# schematic_e00_1.net
KiCad netlist of a schematic drawn in Altium Designer
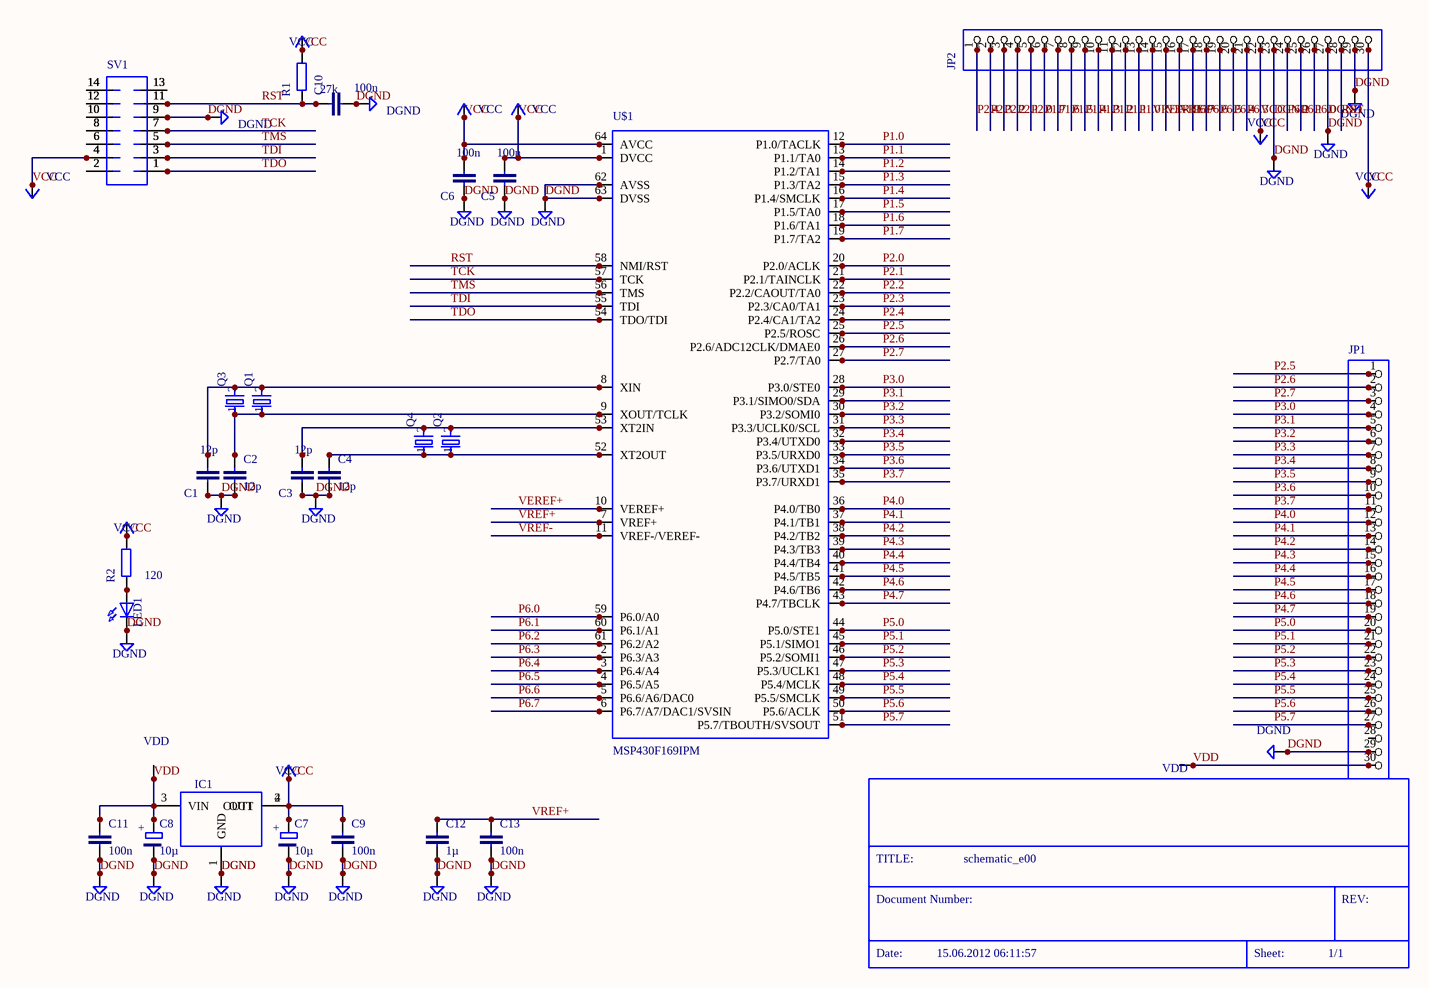
[diagram p0: schematic_e00_1.SchDoc]

(export (version "E")
  (design (tool "Eeschema 10.0.6"))
  (components
    (comp (ref "C1") (value "12p") (footprint "C0805") (libsource (lib "rcl") (part "C-EUC0805")))
    (comp (ref "C2") (value "12p") (footprint "C0805") (libsource (lib "rcl") (part "C-EUC0805")))
    (comp (ref "C3") (value "12p") (footprint "C0805") (libsource (lib "rcl") (part "C-EUC0805")))
    (comp (ref "C4") (value "12p") (footprint "C0805") (libsource (lib "rcl") (part "C-EUC0805")))
    (comp (ref "C5") (value "100n") (footprint "C0805") (libsource (lib "rcl") (part "C-EUC0805")))
    (comp (ref "C6") (value "100n") (footprint "C0805") (libsource (lib "rcl") (part "C-EUC0805")))
    (comp (ref "C7")
      (value "10µ")
      (footprint "153CLV-0505")
      (libsource (lib "rcl") (part "CPOL-EU153CLV-0505"))
    )
    (comp (ref "C8")
      (value "10µ")
      (footprint "153CLV-0505")
      (libsource (lib "rcl") (part "CPOL-EU153CLV-0505"))
    )
    (comp (ref "C9") (value "100n") (footprint "C0805") (libsource (lib "rcl") (part "C-EUC0805")))
    (comp (ref "C10") (value "100n") (footprint "C0805") (libsource (lib "rcl") (part "C-EUC0805")))
    (comp (ref "C11") (value "100n") (footprint "C0805") (libsource (lib "rcl") (part "C-EUC0805")))
    (comp (ref "C12") (value "1µ") (footprint "C0805") (libsource (lib "rcl") (part "C-EUC0805")))
    (comp (ref "C13") (value "100n") (footprint "C0805") (libsource (lib "rcl") (part "C-EUC0805")))
    (comp (ref "FRAME1") (value "~") (libsource (lib "") (part "DINA4_L_1")))
    (comp (ref "IC1") (value "~") (footprint "SOT223") (libsource (lib "national-2") (part "LM1117")))
    (comp (ref "JP1") (value "~") (footprint "1X30") (libsource (lib "pinhead") (part "PINHD-1X30")))
    (comp (ref "JP2") (value "~") (footprint "1X30") (libsource (lib "pinhead") (part "PINHD-1X30")))
    (comp (ref "LED1") (value "~") (footprint "P-LCC-2") (libsource (lib "led") (part "LEDP-LCC-2")))
    (comp (ref "P+1") (value "VCC") (libsource (lib "supply1") (part "VCC")))
    (comp (ref "P+2") (value "VCC") (libsource (lib "supply1") (part "VCC")))
    (comp (ref "P+3") (value "VCC") (libsource (lib "") (part "VCC_1")))
    (comp (ref "P+4") (value "VCC") (libsource (lib "supply1") (part "VCC")))
    (comp (ref "P+5") (value "VCC") (libsource (lib "supply1") (part "VCC")))
    (comp (ref "P+6") (value "VCC") (libsource (lib "") (part "VCC_1")))
    (comp (ref "P+7") (value "VCC") (libsource (lib "") (part "VCC_1")))
    (comp (ref "P+8") (value "VCC") (libsource (lib "supply1") (part "VCC")))
    (comp (ref "Q1") (value "~") (footprint "HC49U70") (libsource (lib "crystal") (part "CRYTALHC49U70")))
    (comp (ref "Q2") (value "~") (footprint "HC49U70") (libsource (lib "crystal") (part "CRYTALHC49U70")))
    (comp (ref "Q3") (value "~") (footprint "HC49UP") (libsource (lib "crystal") (part "CRYTALHC49UP")))
    (comp (ref "Q4") (value "~") (footprint "HC49UP") (libsource (lib "crystal") (part "CRYTALHC49UP")))
    (comp (ref "R1") (value "27k") (footprint "R1206") (libsource (lib "rcl") (part "R-EU_R1206")))
    (comp (ref "R2") (value "120") (footprint "R0805") (libsource (lib "rcl") (part "R-EU_R0805")))
    (comp (ref "SUPPLY1") (value "DGND") (libsource (lib "supply2") (part "DGND")))
    (comp (ref "SUPPLY2") (value "DGND") (libsource (lib "supply2") (part "DGND")))
    (comp (ref "SUPPLY3") (value "DGND") (libsource (lib "supply2") (part "DGND")))
    (comp (ref "SUPPLY4") (value "DGND") (libsource (lib "supply2") (part "DGND")))
    (comp (ref "SUPPLY5") (value "DGND") (libsource (lib "supply2") (part "DGND")))
    (comp (ref "SUPPLY6") (value "DGND") (libsource (lib "supply2") (part "DGND")))
    (comp (ref "SUPPLY7") (value "DGND") (libsource (lib "supply2") (part "DGND")))
    (comp (ref "SUPPLY8") (value "DGND") (libsource (lib "supply2") (part "DGND")))
    (comp (ref "SUPPLY9") (value "VDD") (libsource (lib "supply2") (part "VDD")))
    (comp (ref "SUPPLY10") (value "DGND") (libsource (lib "supply2") (part "DGND")))
    (comp (ref "SUPPLY11") (value "DGND") (libsource (lib "supply2") (part "DGND")))
    (comp (ref "SUPPLY12") (value "DGND") (libsource (lib "supply2") (part "DGND")))
    (comp (ref "SUPPLY13") (value "DGND") (libsource (lib "supply2") (part "DGND")))
    (comp (ref "SUPPLY14") (value "DGND") (libsource (lib "supply2") (part "DGND")))
    (comp (ref "SUPPLY15") (value "DGND") (libsource (lib "supply2") (part "DGND")))
    (comp (ref "SUPPLY16") (value "DGND") (libsource (lib "supply2") (part "DGND")))
    (comp (ref "SUPPLY17") (value "DGND") (libsource (lib "supply2") (part "DGND")))
    (comp (ref "SUPPLY18") (value "DGND") (libsource (lib "supply2") (part "DGND")))
    (comp (ref "SUPPLY19") (value "VDD") (libsource (lib "supply2") (part "VDD")))
    (comp (ref "SUPPLY20") (value "DGND") (libsource (lib "supply2") (part "DGND")))
    (comp (ref "SUPPLY21") (value "DGND") (libsource (lib "supply2") (part "DGND")))
    (comp (ref "SV1") (value "~") (footprint "ML14") (libsource (lib "con-harting-ml") (part "ML14")))
    (comp (ref "U$1")
      (value "MSP430F169IPM")
      (footprint "S-PQFP64-G64")
      (libsource (lib "msp430") (part "MSP430F169IPM"))
    )
  )
  (nets
    (net (code "1") (name "/DGND") (class "Default")
      (node (ref "C1") (pin "1") (pinfunction "1_1") (pintype "passive"))
      (node (ref "C10") (pin "2") (pinfunction "2_2") (pintype "passive"))
      (node (ref "C11") (pin "2") (pinfunction "2_2") (pintype "passive"))
      (node (ref "C12") (pin "2") (pinfunction "2_2") (pintype "passive"))
      (node (ref "C13") (pin "2") (pinfunction "2_2") (pintype "passive"))
      (node (ref "C2") (pin "2") (pinfunction "2_2") (pintype "passive"))
      (node (ref "C3") (pin "1") (pinfunction "1_1") (pintype "passive"))
      (node (ref "C4") (pin "2") (pinfunction "2_2") (pintype "passive"))
      (node (ref "C5") (pin "1") (pinfunction "1_1") (pintype "passive"))
      (node (ref "C6") (pin "1") (pinfunction "1_1") (pintype "passive"))
      (node (ref "C7") (pin "-") (pinfunction "-_-") (pintype "passive"))
      (node (ref "C8") (pin "-") (pinfunction "-_-") (pintype "passive"))
      (node (ref "C9") (pin "2") (pinfunction "2_2") (pintype "passive"))
      (node (ref "IC1") (pin "1") (pinfunction "GND_1") (pintype "passive"))
      (node (ref "JP1") (pin "29") (pinfunction "29_29") (pintype "passive"))
      (node (ref "JP2") (pin "23") (pinfunction "23_23") (pintype "passive"))
      (node (ref "JP2") (pin "27") (pinfunction "27_27") (pintype "passive"))
      (node (ref "JP2") (pin "29") (pinfunction "29_29") (pintype "passive"))
      (node (ref "LED1") (pin "C") (pinfunction "C_C") (pintype "passive"))
      (node (ref "SUPPLY1") (pin "0") (pinfunction "DGND_0") (pintype "passive"))
      (node (ref "SUPPLY10") (pin "0") (pinfunction "DGND_0") (pintype "passive"))
      (node (ref "SUPPLY11") (pin "0") (pinfunction "DGND_0") (pintype "passive"))
      (node (ref "SUPPLY12") (pin "0") (pinfunction "DGND_0") (pintype "passive"))
      (node (ref "SUPPLY13") (pin "0") (pinfunction "DGND_0") (pintype "passive"))
      (node (ref "SUPPLY14") (pin "0") (pinfunction "DGND_0") (pintype "passive"))
      (node (ref "SUPPLY15") (pin "0") (pinfunction "DGND_0") (pintype "passive"))
      (node (ref "SUPPLY16") (pin "0") (pinfunction "DGND_0") (pintype "passive"))
      (node (ref "SUPPLY17") (pin "0") (pinfunction "DGND_0") (pintype "passive"))
      (node (ref "SUPPLY18") (pin "0") (pinfunction "DGND_0") (pintype "passive"))
      (node (ref "SUPPLY2") (pin "0") (pinfunction "DGND_0") (pintype "passive"))
      (node (ref "SUPPLY20") (pin "0") (pinfunction "DGND_0") (pintype "passive"))
      (node (ref "SUPPLY21") (pin "0") (pinfunction "DGND_0") (pintype "passive"))
      (node (ref "SUPPLY3") (pin "0") (pinfunction "DGND_0") (pintype "passive"))
      (node (ref "SUPPLY4") (pin "0") (pinfunction "DGND_0") (pintype "passive"))
      (node (ref "SUPPLY5") (pin "0") (pinfunction "DGND_0") (pintype "passive"))
      (node (ref "SUPPLY6") (pin "0") (pinfunction "DGND_0") (pintype "passive"))
      (node (ref "SUPPLY7") (pin "0") (pinfunction "DGND_0") (pintype "passive"))
      (node (ref "SUPPLY8") (pin "0") (pinfunction "DGND_0") (pintype "passive"))
      (node (ref "SV1") (pin "9") (pinfunction "9_9") (pintype "passive"))
      (node (ref "U$1") (pin "62") (pinfunction "AVSS_62") (pintype "passive"))
      (node (ref "U$1") (pin "63") (pinfunction "DVSS_63") (pintype "passive"))
    )
    (net (code "2") (name "/P1.0") (class "Default")
      (node (ref "JP2") (pin "13") (pinfunction "13_13") (pintype "passive"))
      (node (ref "U$1") (pin "12") (pinfunction "P1.0/TACLK_12") (pintype "passive"))
    )
    (net (code "3") (name "/P1.1") (class "Default")
      (node (ref "JP2") (pin "12") (pinfunction "12_12") (pintype "passive"))
      (node (ref "U$1") (pin "13") (pinfunction "P1.1/TA0_13") (pintype "passive"))
    )
    (net (code "4") (name "/P1.2") (class "Default")
      (node (ref "JP2") (pin "11") (pinfunction "11_11") (pintype "passive"))
      (node (ref "U$1") (pin "14") (pinfunction "P1.2/TA1_14") (pintype "passive"))
    )
    (net (code "5") (name "/P1.3") (class "Default")
      (node (ref "JP2") (pin "10") (pinfunction "10_10") (pintype "passive"))
      (node (ref "U$1") (pin "15") (pinfunction "P1.3/TA2_15") (pintype "passive"))
    )
    (net (code "6") (name "/P1.4") (class "Default")
      (node (ref "JP2") (pin "9") (pinfunction "9_9") (pintype "passive"))
      (node (ref "U$1") (pin "16") (pinfunction "P1.4/SMCLK_16") (pintype "passive"))
    )
    (net (code "7") (name "/P1.5") (class "Default")
      (node (ref "JP2") (pin "8") (pinfunction "8_8") (pintype "passive"))
      (node (ref "U$1") (pin "17") (pinfunction "P1.5/TA0_17") (pintype "passive"))
    )
    (net (code "8") (name "/P1.6") (class "Default")
      (node (ref "JP2") (pin "7") (pinfunction "7_7") (pintype "passive"))
      (node (ref "U$1") (pin "18") (pinfunction "P1.6/TA1_18") (pintype "passive"))
    )
    (net (code "9") (name "/P1.7") (class "Default")
      (node (ref "JP2") (pin "6") (pinfunction "6_6") (pintype "passive"))
      (node (ref "U$1") (pin "19") (pinfunction "P1.7/TA2_19") (pintype "passive"))
    )
    (net (code "10") (name "/P2.0") (class "Default")
      (node (ref "JP2") (pin "5") (pinfunction "5_5") (pintype "passive"))
      (node (ref "U$1") (pin "20") (pinfunction "P2.0/ACLK_20") (pintype "passive"))
    )
    (net (code "11") (name "/P2.1") (class "Default")
      (node (ref "JP2") (pin "4") (pinfunction "4_4") (pintype "passive"))
      (node (ref "U$1") (pin "21") (pinfunction "P2.1/TAINCLK_21") (pintype "passive"))
    )
    (net (code "12") (name "/P2.2") (class "Default")
      (node (ref "JP2") (pin "3") (pinfunction "3_3") (pintype "passive"))
      (node (ref "U$1") (pin "22") (pinfunction "P2.2/CAOUT/TA0_22") (pintype "passive"))
    )
    (net (code "13") (name "/P2.3") (class "Default")
      (node (ref "JP2") (pin "2") (pinfunction "2_2") (pintype "passive"))
      (node (ref "U$1") (pin "23") (pinfunction "P2.3/CA0/TA1_23") (pintype "passive"))
    )
    (net (code "14") (name "/P2.4") (class "Default")
      (node (ref "JP2") (pin "1") (pinfunction "1_1") (pintype "passive"))
      (node (ref "U$1") (pin "24") (pinfunction "P2.4/CA1/TA2_24") (pintype "passive"))
    )
    (net (code "15") (name "/P2.5") (class "Default")
      (node (ref "JP1") (pin "1") (pinfunction "1_1") (pintype "passive"))
      (node (ref "U$1") (pin "25") (pinfunction "P2.5/ROSC_25") (pintype "passive"))
    )
    (net (code "16") (name "/P2.6") (class "Default")
      (node (ref "JP1") (pin "2") (pinfunction "2_2") (pintype "passive"))
      (node (ref "U$1") (pin "26") (pinfunction "P2.6/ADC12CLK/DMAE0_26") (pintype "passive"))
    )
    (net (code "17") (name "/P2.7") (class "Default")
      (node (ref "JP1") (pin "3") (pinfunction "3_3") (pintype "passive"))
      (node (ref "U$1") (pin "27") (pinfunction "P2.7/TA0_27") (pintype "passive"))
    )
    (net (code "18") (name "/P3.0") (class "Default")
      (node (ref "JP1") (pin "4") (pinfunction "4_4") (pintype "passive"))
      (node (ref "U$1") (pin "28") (pinfunction "P3.0/STE0_28") (pintype "passive"))
    )
    (net (code "19") (name "/P3.1") (class "Default")
      (node (ref "JP1") (pin "5") (pinfunction "5_5") (pintype "passive"))
      (node (ref "U$1") (pin "29") (pinfunction "P3.1/SIMO0/SDA_29") (pintype "passive"))
    )
    (net (code "20") (name "/P3.2") (class "Default")
      (node (ref "JP1") (pin "6") (pinfunction "6_6") (pintype "passive"))
      (node (ref "U$1") (pin "30") (pinfunction "P3.2/SOMI0_30") (pintype "passive"))
    )
    (net (code "21") (name "/P3.3") (class "Default")
      (node (ref "JP1") (pin "7") (pinfunction "7_7") (pintype "passive"))
      (node (ref "U$1") (pin "31") (pinfunction "P3.3/UCLK0/SCL_31") (pintype "passive"))
    )
    (net (code "22") (name "/P3.4") (class "Default")
      (node (ref "JP1") (pin "8") (pinfunction "8_8") (pintype "passive"))
      (node (ref "U$1") (pin "32") (pinfunction "P3.4/UTXD0_32") (pintype "passive"))
    )
    (net (code "23") (name "/P3.5") (class "Default")
      (node (ref "JP1") (pin "9") (pinfunction "9_9") (pintype "passive"))
      (node (ref "U$1") (pin "33") (pinfunction "P3.5/URXD0_33") (pintype "passive"))
    )
    (net (code "24") (name "/P3.6") (class "Default")
      (node (ref "JP1") (pin "10") (pinfunction "10_10") (pintype "passive"))
      (node (ref "U$1") (pin "34") (pinfunction "P3.6/UTXD1_34") (pintype "passive"))
    )
    (net (code "25") (name "/P3.7") (class "Default")
      (node (ref "JP1") (pin "11") (pinfunction "11_11") (pintype "passive"))
      (node (ref "U$1") (pin "35") (pinfunction "P3.7/URXD1_35") (pintype "passive"))
    )
    (net (code "26") (name "/P4.0") (class "Default")
      (node (ref "JP1") (pin "12") (pinfunction "12_12") (pintype "passive"))
      (node (ref "U$1") (pin "36") (pinfunction "P4.0/TB0_36") (pintype "passive"))
    )
    (net (code "27") (name "/P4.1") (class "Default")
      (node (ref "JP1") (pin "13") (pinfunction "13_13") (pintype "passive"))
      (node (ref "U$1") (pin "37") (pinfunction "P4.1/TB1_37") (pintype "passive"))
    )
    (net (code "28") (name "/P4.2") (class "Default")
      (node (ref "JP1") (pin "14") (pinfunction "14_14") (pintype "passive"))
      (node (ref "U$1") (pin "38") (pinfunction "P4.2/TB2_38") (pintype "passive"))
    )
    (net (code "29") (name "/P4.3") (class "Default")
      (node (ref "JP1") (pin "15") (pinfunction "15_15") (pintype "passive"))
      (node (ref "U$1") (pin "39") (pinfunction "P4.3/TB3_39") (pintype "passive"))
    )
    (net (code "30") (name "/P4.4") (class "Default")
      (node (ref "JP1") (pin "16") (pinfunction "16_16") (pintype "passive"))
      (node (ref "U$1") (pin "40") (pinfunction "P4.4/TB4_40") (pintype "passive"))
    )
    (net (code "31") (name "/P4.5") (class "Default")
      (node (ref "JP1") (pin "17") (pinfunction "17_17") (pintype "passive"))
      (node (ref "U$1") (pin "41") (pinfunction "P4.5/TB5_41") (pintype "passive"))
    )
    (net (code "32") (name "/P4.6") (class "Default")
      (node (ref "JP1") (pin "18") (pinfunction "18_18") (pintype "passive"))
      (node (ref "U$1") (pin "42") (pinfunction "P4.6/TB6_42") (pintype "passive"))
    )
    (net (code "33") (name "/P4.7") (class "Default")
      (node (ref "JP1") (pin "19") (pinfunction "19_19") (pintype "passive"))
      (node (ref "U$1") (pin "43") (pinfunction "P4.7/TBCLK_43") (pintype "passive"))
    )
    (net (code "34") (name "/P5.0") (class "Default")
      (node (ref "JP1") (pin "20") (pinfunction "20_20") (pintype "passive"))
      (node (ref "U$1") (pin "44") (pinfunction "P5.0/STE1_44") (pintype "passive"))
    )
    (net (code "35") (name "/P5.1") (class "Default")
      (node (ref "JP1") (pin "21") (pinfunction "21_21") (pintype "passive"))
      (node (ref "U$1") (pin "45") (pinfunction "P5.1/SIMO1_45") (pintype "passive"))
    )
    (net (code "36") (name "/P5.2") (class "Default")
      (node (ref "JP1") (pin "22") (pinfunction "22_22") (pintype "passive"))
      (node (ref "U$1") (pin "46") (pinfunction "P5.2/SOMI1_46") (pintype "passive"))
    )
    (net (code "37") (name "/P5.3") (class "Default")
      (node (ref "JP1") (pin "23") (pinfunction "23_23") (pintype "passive"))
      (node (ref "U$1") (pin "47") (pinfunction "P5.3/UCLK1_47") (pintype "passive"))
    )
    (net (code "38") (name "/P5.4") (class "Default")
      (node (ref "JP1") (pin "24") (pinfunction "24_24") (pintype "passive"))
      (node (ref "U$1") (pin "48") (pinfunction "P5.4/MCLK_48") (pintype "passive"))
    )
    (net (code "39") (name "/P5.5") (class "Default")
      (node (ref "JP1") (pin "25") (pinfunction "25_25") (pintype "passive"))
      (node (ref "U$1") (pin "49") (pinfunction "P5.5/SMCLK_49") (pintype "passive"))
    )
    (net (code "40") (name "/P5.6") (class "Default")
      (node (ref "JP1") (pin "26") (pinfunction "26_26") (pintype "passive"))
      (node (ref "U$1") (pin "50") (pinfunction "P5.6/ACLK_50") (pintype "passive"))
    )
    (net (code "41") (name "/P5.7") (class "Default")
      (node (ref "JP1") (pin "27") (pinfunction "27_27") (pintype "passive"))
      (node (ref "U$1") (pin "51") (pinfunction "P5.7/TBOUTH/SVSOUT_51") (pintype "passive"))
    )
    (net (code "42") (name "/P6.0") (class "Default")
      (node (ref "JP2") (pin "26") (pinfunction "26_26") (pintype "passive"))
      (node (ref "U$1") (pin "59") (pinfunction "P6.0/A0_59") (pintype "passive"))
    )
    (net (code "43") (name "/P6.1") (class "Default")
      (node (ref "JP2") (pin "25") (pinfunction "25_25") (pintype "passive"))
      (node (ref "U$1") (pin "60") (pinfunction "P6.1/A1_60") (pintype "passive"))
    )
    (net (code "44") (name "/P6.2") (class "Default")
      (node (ref "JP2") (pin "24") (pinfunction "24_24") (pintype "passive"))
      (node (ref "U$1") (pin "61") (pinfunction "P6.2/A2_61") (pintype "passive"))
    )
    (net (code "45") (name "/P6.3") (class "Default")
      (node (ref "JP2") (pin "21") (pinfunction "21_21") (pintype "passive"))
      (node (ref "U$1") (pin "2") (pinfunction "P6.3/A3_2") (pintype "passive"))
    )
    (net (code "46") (name "/P6.4") (class "Default")
      (node (ref "JP2") (pin "20") (pinfunction "20_20") (pintype "passive"))
      (node (ref "U$1") (pin "3") (pinfunction "P6.4/A4_3") (pintype "passive"))
    )
    (net (code "47") (name "/P6.5") (class "Default")
      (node (ref "JP2") (pin "19") (pinfunction "19_19") (pintype "passive"))
      (node (ref "U$1") (pin "4") (pinfunction "P6.5/A5_4") (pintype "passive"))
    )
    (net (code "48") (name "/P6.6") (class "Default")
      (node (ref "JP2") (pin "18") (pinfunction "18_18") (pintype "passive"))
      (node (ref "U$1") (pin "5") (pinfunction "P6.6/A6/DAC0_5") (pintype "passive"))
    )
    (net (code "49") (name "/P6.7") (class "Default")
      (node (ref "JP2") (pin "17") (pinfunction "17_17") (pintype "passive"))
      (node (ref "U$1") (pin "6") (pinfunction "P6.7/A7/DAC1/SVSIN_6") (pintype "passive"))
    )
    (net (code "50") (name "/RST") (class "Default")
      (node (ref "C10") (pin "1") (pinfunction "1_1") (pintype "passive"))
      (node (ref "JP2") (pin "28") (pinfunction "28_28") (pintype "passive"))
      (node (ref "R1") (pin "1") (pinfunction "1_1") (pintype "passive"))
      (node (ref "SV1") (pin "11") (pinfunction "11_11") (pintype "passive"))
      (node (ref "U$1") (pin "58") (pinfunction "NMI/RST_58") (pintype "passive"))
    )
    (net (code "51") (name "/TCK") (class "Default")
      (node (ref "SV1") (pin "7") (pinfunction "7_7") (pintype "passive"))
      (node (ref "U$1") (pin "57") (pinfunction "TCK_57") (pintype "passive"))
    )
    (net (code "52") (name "/TDI") (class "Default")
      (node (ref "SV1") (pin "3") (pinfunction "3_3") (pintype "passive"))
      (node (ref "U$1") (pin "55") (pinfunction "TDI_55") (pintype "passive"))
    )
    (net (code "53") (name "/TDO") (class "Default")
      (node (ref "SV1") (pin "1") (pinfunction "1_1") (pintype "passive"))
      (node (ref "U$1") (pin "54") (pinfunction "TDO/TDI_54") (pintype "passive"))
    )
    (net (code "54") (name "/TMS") (class "Default")
      (node (ref "SV1") (pin "5") (pinfunction "5_5") (pintype "passive"))
      (node (ref "U$1") (pin "56") (pinfunction "TMS_56") (pintype "passive"))
    )
    (net (code "55") (name "/VCC") (class "Default")
      (node (ref "C5") (pin "2") (pinfunction "2_2") (pintype "passive"))
      (node (ref "C6") (pin "2") (pinfunction "2_2") (pintype "passive"))
      (node (ref "C7") (pin "+") (pinfunction "+_+") (pintype "passive"))
      (node (ref "C9") (pin "1") (pinfunction "1_1") (pintype "passive"))
      (node (ref "IC1") (pin "2") (pinfunction "OUT_2") (pintype "passive"))
      (node (ref "IC1") (pin "4") (pinfunction "OUT1_4") (pintype "passive"))
      (node (ref "JP2") (pin "22") (pinfunction "22_22") (pintype "passive"))
      (node (ref "JP2") (pin "30") (pinfunction "30_30") (pintype "passive"))
      (node (ref "P+1") (pin "0") (pinfunction "VCC_0") (pintype "passive"))
      (node (ref "P+2") (pin "0") (pinfunction "VCC_0") (pintype "passive"))
      (node (ref "P+3") (pin "0") (pinfunction "VCC_0") (pintype "passive"))
      (node (ref "P+4") (pin "0") (pinfunction "VCC_0") (pintype "passive"))
      (node (ref "P+5") (pin "0") (pinfunction "VCC_0") (pintype "passive"))
      (node (ref "P+6") (pin "0") (pinfunction "VCC_0") (pintype "passive"))
      (node (ref "P+7") (pin "0") (pinfunction "VCC_0") (pintype "passive"))
      (node (ref "P+8") (pin "0") (pinfunction "VCC_0") (pintype "passive"))
      (node (ref "R1") (pin "2") (pinfunction "2_2") (pintype "passive"))
      (node (ref "R2") (pin "2") (pinfunction "2_2") (pintype "passive"))
      (node (ref "SV1") (pin "4") (pinfunction "4_4") (pintype "passive"))
      (node (ref "U$1") (pin "1") (pinfunction "DVCC_1") (pintype "passive"))
      (node (ref "U$1") (pin "64") (pinfunction "AVCC_64") (pintype "passive"))
    )
    (net (code "56") (name "/VDD") (class "Default")
      (node (ref "C11") (pin "1") (pinfunction "1_1") (pintype "passive"))
      (node (ref "C8") (pin "+") (pinfunction "+_+") (pintype "passive"))
      (node (ref "IC1") (pin "3") (pinfunction "VIN_3") (pintype "passive"))
      (node (ref "JP1") (pin "30") (pinfunction "30_30") (pintype "passive"))
      (node (ref "SUPPLY19") (pin "0") (pinfunction "VDD_0") (pintype "passive"))
      (node (ref "SUPPLY9") (pin "0") (pinfunction "VDD_0") (pintype "passive"))
    )
    (net (code "57") (name "/VEREF+") (class "Default")
      (node (ref "JP2") (pin "15") (pinfunction "15_15") (pintype "passive"))
      (node (ref "U$1") (pin "10") (pinfunction "VEREF+_10") (pintype "passive"))
    )
    (net (code "58") (name "/VREF+") (class "Default")
      (node (ref "C12") (pin "1") (pinfunction "1_1") (pintype "passive"))
      (node (ref "C13") (pin "1") (pinfunction "1_1") (pintype "passive"))
      (node (ref "JP2") (pin "16") (pinfunction "16_16") (pintype "passive"))
      (node (ref "U$1") (pin "7") (pinfunction "VREF+_7") (pintype "passive"))
    )
    (net (code "59") (name "/VREF-") (class "Default")
      (node (ref "JP2") (pin "14") (pinfunction "14_14") (pintype "passive"))
      (node (ref "U$1") (pin "11") (pinfunction "VREF-/VEREF-_11") (pintype "passive"))
    )
    (net (code "60") (name "Net-(LED1-PadA)") (class "Default")
      (node (ref "LED1") (pin "A") (pinfunction "A_A") (pintype "passive"))
      (node (ref "R2") (pin "1") (pinfunction "1_1") (pintype "passive"))
    )
    (net (code "61") (name "Net-(SV1-Pad2)") (class "Default")
      (node (ref "SV1") (pin "2") (pinfunction "2_2") (pintype "passive"))
    )
    (net (code "62") (name "Net-(SV1-Pad6)") (class "Default")
      (node (ref "SV1") (pin "6") (pinfunction "6_6") (pintype "passive"))
    )
    (net (code "63") (name "Net-(SV1-Pad8)") (class "Default")
      (node (ref "SV1") (pin "8") (pinfunction "8_8") (pintype "passive"))
    )
    (net (code "64") (name "Net-(SV1-Pad10)") (class "Default")
      (node (ref "SV1") (pin "10") (pinfunction "10_10") (pintype "passive"))
    )
    (net (code "65") (name "Net-(SV1-Pad12)") (class "Default")
      (node (ref "SV1") (pin "12") (pinfunction "12_12") (pintype "passive"))
    )
    (net (code "66") (name "Net-(SV1-Pad13)") (class "Default")
      (node (ref "SV1") (pin "13") (pinfunction "13_13") (pintype "passive"))
    )
    (net (code "67") (name "Net-(SV1-Pad14)") (class "Default")
      (node (ref "SV1") (pin "14") (pinfunction "14_14") (pintype "passive"))
    )
    (net (code "68") (name "Net-(U$1-XIN)") (class "Default")
      (node (ref "C1") (pin "2") (pinfunction "2_2") (pintype "passive"))
      (node (ref "Q1") (pin "2") (pinfunction "2_2") (pintype "passive"))
      (node (ref "Q3") (pin "2") (pinfunction "2_2") (pintype "passive"))
      (node (ref "U$1") (pin "8") (pinfunction "XIN_8") (pintype "passive"))
    )
    (net (code "69") (name "Net-(U$1-XOUT{slash}TCLK)") (class "Default")
      (node (ref "C2") (pin "1") (pinfunction "1_1") (pintype "passive"))
      (node (ref "Q1") (pin "1") (pinfunction "1_1") (pintype "passive"))
      (node (ref "Q3") (pin "1") (pinfunction "1_1") (pintype "passive"))
      (node (ref "U$1") (pin "9") (pinfunction "XOUT/TCLK_9") (pintype "passive"))
    )
    (net (code "70") (name "Net-(U$1-XT2IN)") (class "Default")
      (node (ref "C3") (pin "2") (pinfunction "2_2") (pintype "passive"))
      (node (ref "Q2") (pin "2") (pinfunction "2_2") (pintype "passive"))
      (node (ref "Q4") (pin "2") (pinfunction "2_2") (pintype "passive"))
      (node (ref "U$1") (pin "53") (pinfunction "XT2IN_53") (pintype "passive"))
    )
    (net (code "71") (name "Net-(U$1-XT2OUT)") (class "Default")
      (node (ref "C4") (pin "1") (pinfunction "1_1") (pintype "passive"))
      (node (ref "Q2") (pin "1") (pinfunction "1_1") (pintype "passive"))
      (node (ref "Q4") (pin "1") (pinfunction "1_1") (pintype "passive"))
      (node (ref "U$1") (pin "52") (pinfunction "XT2OUT_52") (pintype "passive"))
    )
    (net (code "72") (name "unconnected-(JP1-Pad28)") (class "Default")
      (node (ref "JP1") (pin "28") (pinfunction "28_28") (pintype "passive"))
    )
  )
)
